# mux_ic.net
KiCad netlist of a schematic drawn in EAGLE
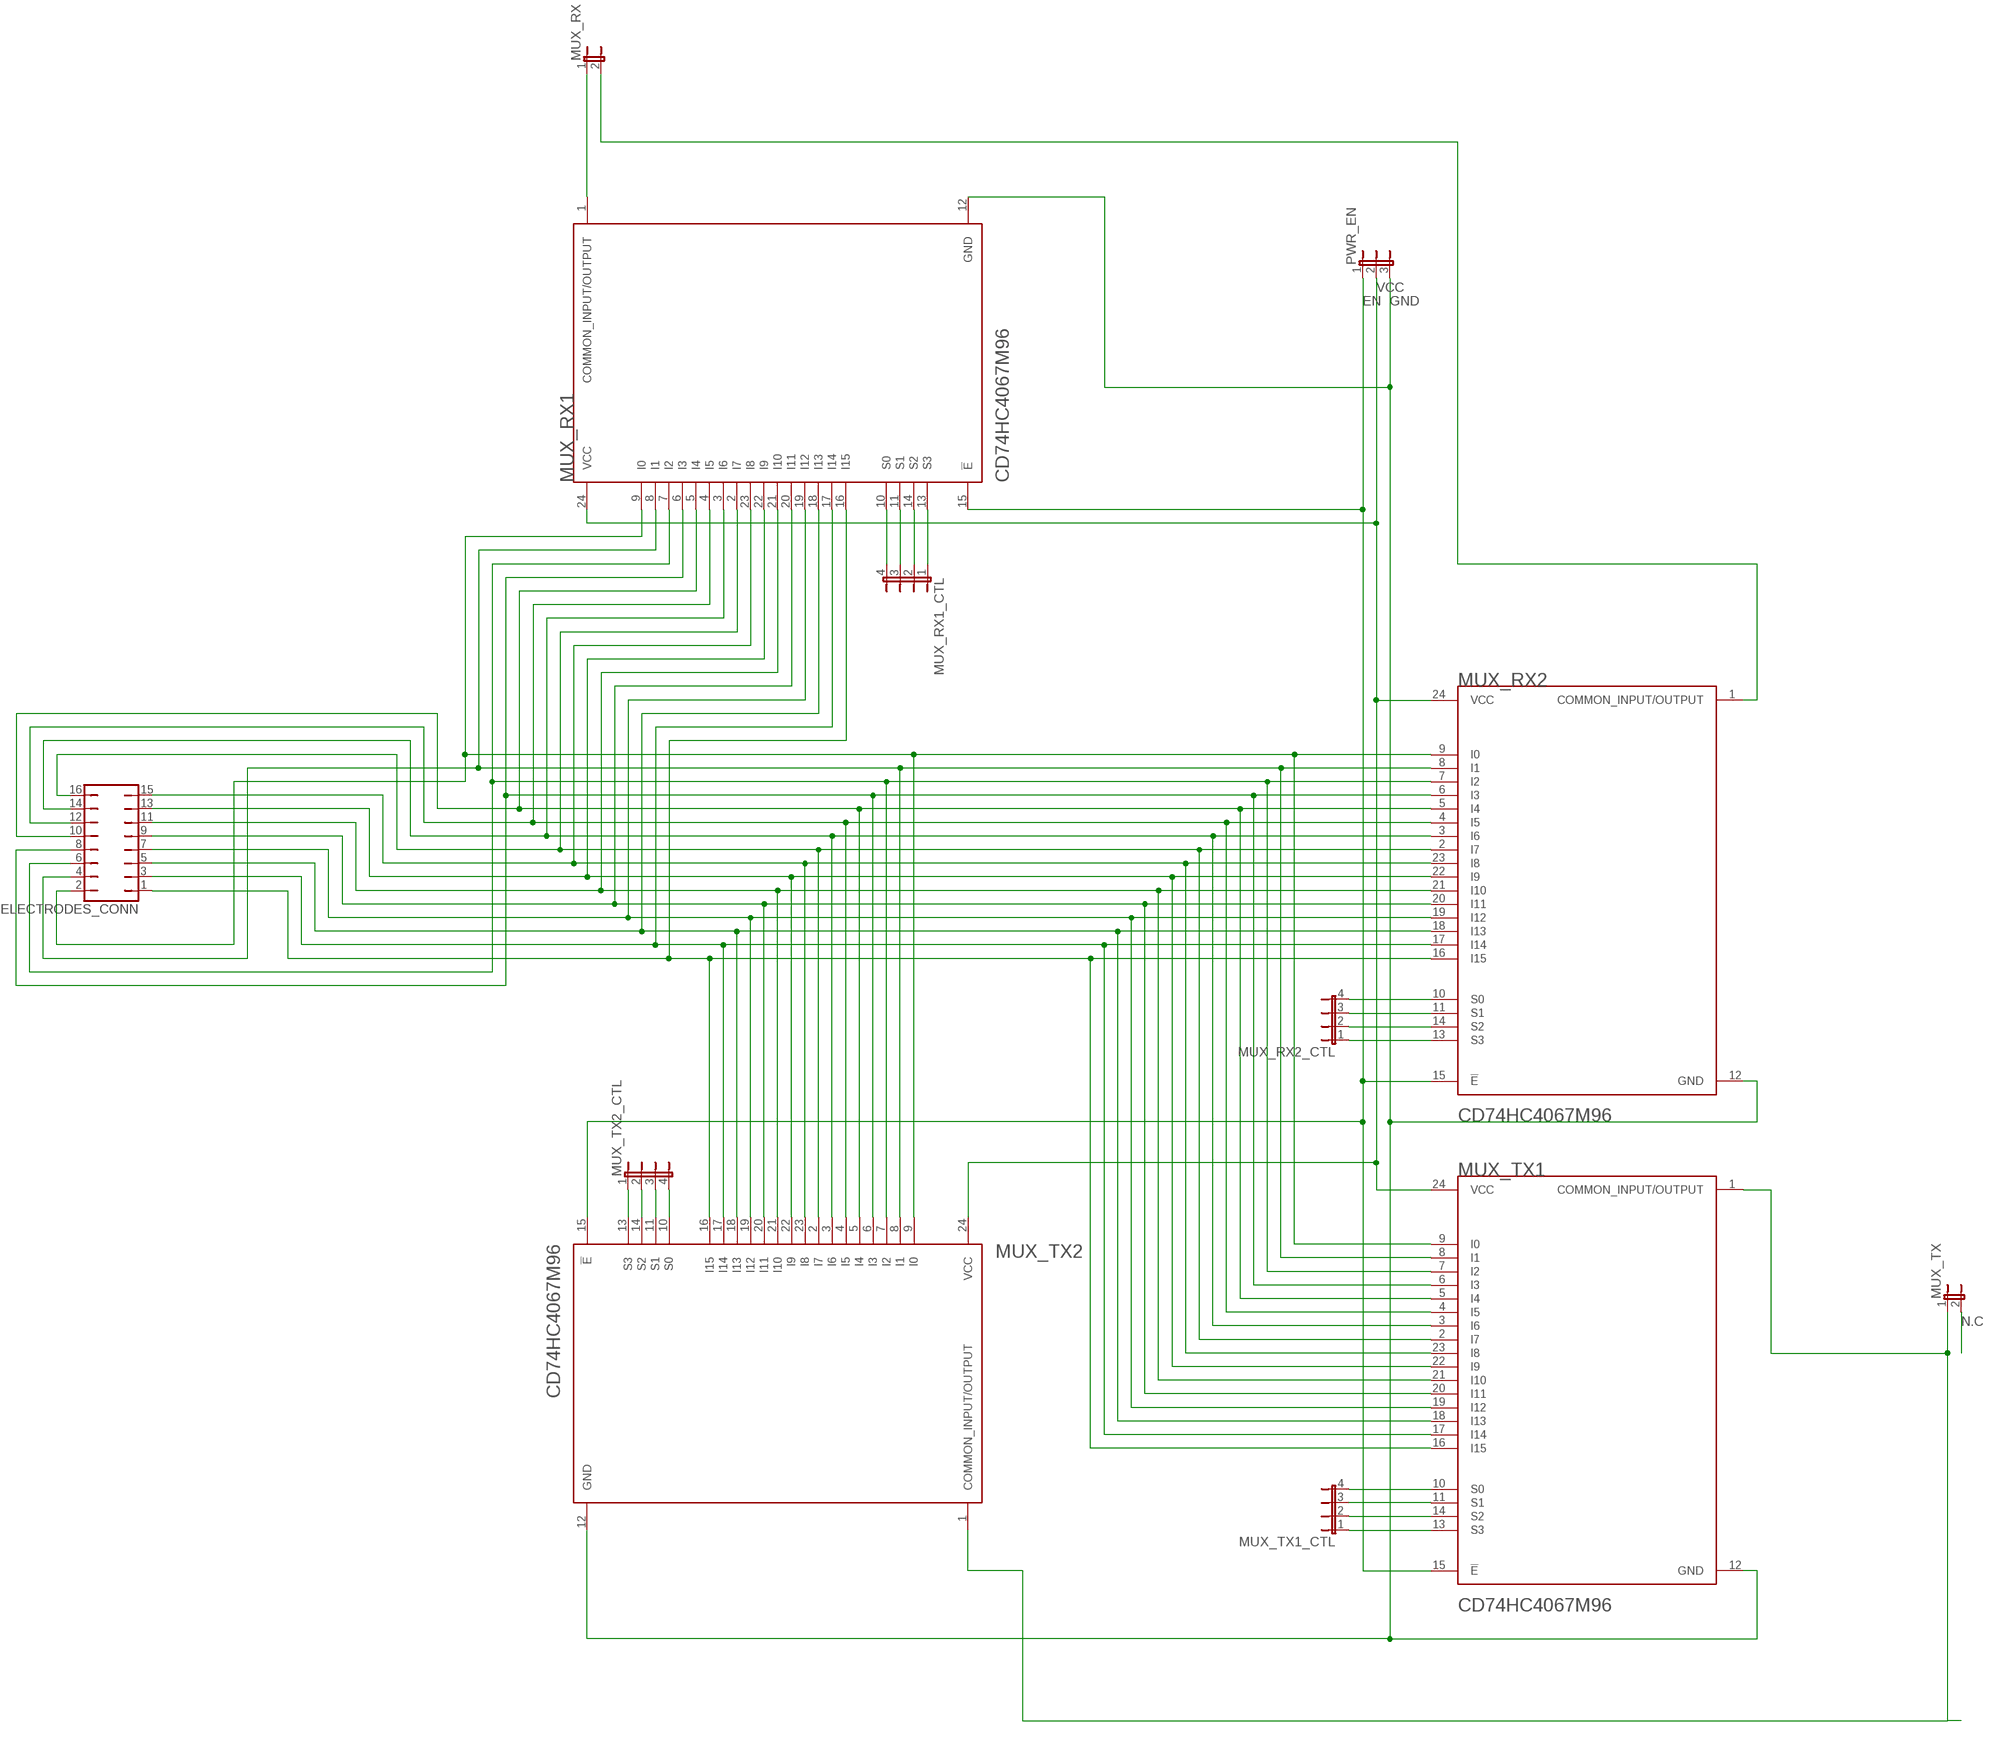
[diagram p0: schematic, sheet 1]

(export (version "E")
  (design (tool "Eeschema 10.0.6"))
  (components
    (comp (ref "ELECTRODES_CONN")
      (value "JP8Q")
      (footprint "eagle-import:JP8Q")
      (libsource (lib "eagle-import") (part "JP8Q"))
    )
    (comp (ref "MUX_RX")
      (value "JP1E")
      (footprint "eagle-import:JP1")
      (libsource (lib "eagle-import") (part "JP1E"))
    )
    (comp (ref "MUX_RX1")
      (value "TEXAS_INSTRUMENTS_CD74HC4067M96TEXAS_INSTRUMENTS_CD74HC4067M96_0_0")
      (footprint "eagle-import:TEXAS_INSTRUMENTS_CD74HC4067M96_0")
      (fields
        (field (name "DIGIKEY_PART_NUMBER") "296-29408-1-ND")
        (field (name "MF") "Texas Instruments")
        (field (name "MOUSER_PART_NUMBER") "595-CD74HC4067M96")
      )
      (libsource (lib "eagle-import") (part "TEXAS_INSTRUMENTS_CD74HC4067M96TEXAS_INSTRUMENTS_CD74HC4067M96_0_0"))
    )
    (comp (ref "MUX_RX1_CTL")
      (value "JP4E")
      (footprint "eagle-import:JP4")
      (libsource (lib "eagle-import") (part "JP4E"))
    )
    (comp (ref "MUX_RX2")
      (value "TEXAS_INSTRUMENTS_CD74HC4067M96TEXAS_INSTRUMENTS_CD74HC4067M96_0_0")
      (footprint "eagle-import:TEXAS_INSTRUMENTS_CD74HC4067M96_0")
      (fields
        (field (name "DIGIKEY_PART_NUMBER") "296-29408-1-ND")
        (field (name "MF") "Texas Instruments")
        (field (name "MOUSER_PART_NUMBER") "595-CD74HC4067M96")
      )
      (libsource (lib "eagle-import") (part "TEXAS_INSTRUMENTS_CD74HC4067M96TEXAS_INSTRUMENTS_CD74HC4067M96_0_0"))
    )
    (comp (ref "MUX_RX2_CTL")
      (value "JP4E")
      (footprint "eagle-import:JP4")
      (libsource (lib "eagle-import") (part "JP4E"))
    )
    (comp (ref "MUX_TX")
      (value "JP1E")
      (footprint "eagle-import:JP1")
      (libsource (lib "eagle-import") (part "JP1E"))
    )
    (comp (ref "MUX_TX1")
      (value "TEXAS_INSTRUMENTS_CD74HC4067M96TEXAS_INSTRUMENTS_CD74HC4067M96_0_0")
      (footprint "eagle-import:TEXAS_INSTRUMENTS_CD74HC4067M96_0")
      (fields
        (field (name "DIGIKEY_PART_NUMBER") "296-29408-1-ND")
        (field (name "MF") "Texas Instruments")
        (field (name "MOUSER_PART_NUMBER") "595-CD74HC4067M96")
      )
      (libsource (lib "eagle-import") (part "TEXAS_INSTRUMENTS_CD74HC4067M96TEXAS_INSTRUMENTS_CD74HC4067M96_0_0"))
    )
    (comp (ref "MUX_TX1_CTL")
      (value "JP4E")
      (footprint "eagle-import:JP4")
      (libsource (lib "eagle-import") (part "JP4E"))
    )
    (comp (ref "MUX_TX2")
      (value "TEXAS_INSTRUMENTS_CD74HC4067M96TEXAS_INSTRUMENTS_CD74HC4067M96_0_0")
      (footprint "eagle-import:TEXAS_INSTRUMENTS_CD74HC4067M96_0")
      (fields
        (field (name "DIGIKEY_PART_NUMBER") "296-29408-1-ND")
        (field (name "MF") "Texas Instruments")
        (field (name "MOUSER_PART_NUMBER") "595-CD74HC4067M96")
      )
      (libsource (lib "eagle-import") (part "TEXAS_INSTRUMENTS_CD74HC4067M96TEXAS_INSTRUMENTS_CD74HC4067M96_0_0"))
    )
    (comp (ref "MUX_TX2_CTL")
      (value "JP4E")
      (footprint "eagle-import:JP4")
      (libsource (lib "eagle-import") (part "JP4E"))
    )
    (comp (ref "PWR_EN")
      (value "JP2W")
      (footprint "eagle-import:JP2W")
      (libsource (lib "eagle-import") (part "JP2W"))
    )
  )
  (nets
    (net (code "1") (name "/EN") (class "Default")
      (node (ref "MUX_RX1") (pin "15") (pinfunction "~{E}_15") (pintype "input"))
      (node (ref "MUX_RX2") (pin "15") (pinfunction "~{E}_15") (pintype "input"))
      (node (ref "MUX_TX1") (pin "15") (pinfunction "~{E}_15") (pintype "input"))
      (node (ref "MUX_TX2") (pin "15") (pinfunction "~{E}_15") (pintype "input"))
      (node (ref "PWR_EN") (pin "1") (pinfunction "1_1") (pintype "passive"))
    )
    (net (code "2") (name "/GND") (class "Default")
      (node (ref "MUX_RX1") (pin "12") (pinfunction "GND_12") (pintype "power_in"))
      (node (ref "MUX_RX2") (pin "12") (pinfunction "GND_12") (pintype "power_in"))
      (node (ref "MUX_TX1") (pin "12") (pinfunction "GND_12") (pintype "power_in"))
      (node (ref "MUX_TX2") (pin "12") (pinfunction "GND_12") (pintype "power_in"))
      (node (ref "PWR_EN") (pin "3") (pinfunction "3_3") (pintype "passive"))
    )
    (net (code "3") (name "/N$2") (class "Default")
      (node (ref "ELECTRODES_CONN") (pin "1") (pinfunction "1_1") (pintype "passive"))
      (node (ref "ELECTRODES_CONN") (pin "10") (pinfunction "10_10") (pintype "passive"))
      (node (ref "ELECTRODES_CONN") (pin "12") (pinfunction "12_12") (pintype "passive"))
      (node (ref "ELECTRODES_CONN") (pin "13") (pinfunction "13_13") (pintype "passive"))
      (node (ref "ELECTRODES_CONN") (pin "14") (pinfunction "14_14") (pintype "passive"))
      (node (ref "ELECTRODES_CONN") (pin "15") (pinfunction "15_15") (pintype "passive"))
      (node (ref "ELECTRODES_CONN") (pin "16") (pinfunction "16_16") (pintype "passive"))
      (node (ref "ELECTRODES_CONN") (pin "3") (pinfunction "3_3") (pintype "passive"))
      (node (ref "ELECTRODES_CONN") (pin "4") (pinfunction "4_4") (pintype "passive"))
      (node (ref "ELECTRODES_CONN") (pin "5") (pinfunction "5_5") (pintype "passive"))
      (node (ref "ELECTRODES_CONN") (pin "6") (pinfunction "6_6") (pintype "passive"))
      (node (ref "ELECTRODES_CONN") (pin "7") (pinfunction "7_7") (pintype "passive"))
      (node (ref "ELECTRODES_CONN") (pin "8") (pinfunction "8_8") (pintype "passive"))
      (node (ref "ELECTRODES_CONN") (pin "9") (pinfunction "9_9") (pintype "passive"))
      (node (ref "MUX_RX1") (pin "16") (pinfunction "I15_16") (pintype "input"))
      (node (ref "MUX_RX1") (pin "17") (pinfunction "I14_17") (pintype "input"))
      (node (ref "MUX_RX1") (pin "18") (pinfunction "I13_18") (pintype "input"))
      (node (ref "MUX_RX1") (pin "19") (pinfunction "I12_19") (pintype "input"))
      (node (ref "MUX_RX1") (pin "2") (pinfunction "I7_2") (pintype "input"))
      (node (ref "MUX_RX1") (pin "20") (pinfunction "I11_20") (pintype "input"))
      (node (ref "MUX_RX1") (pin "22") (pinfunction "I9_22") (pintype "input"))
      (node (ref "MUX_RX1") (pin "23") (pinfunction "I8_23") (pintype "input"))
      (node (ref "MUX_RX1") (pin "3") (pinfunction "I6_3") (pintype "input"))
      (node (ref "MUX_RX1") (pin "4") (pinfunction "I5_4") (pintype "input"))
      (node (ref "MUX_RX1") (pin "5") (pinfunction "I4_5") (pintype "input"))
      (node (ref "MUX_RX1") (pin "6") (pinfunction "I3_6") (pintype "input"))
      (node (ref "MUX_RX1") (pin "7") (pinfunction "I2_7") (pintype "input"))
      (node (ref "MUX_RX1") (pin "8") (pinfunction "I1_8") (pintype "input"))
      (node (ref "MUX_RX2") (pin "16") (pinfunction "I15_16") (pintype "input"))
      (node (ref "MUX_RX2") (pin "17") (pinfunction "I14_17") (pintype "input"))
      (node (ref "MUX_RX2") (pin "18") (pinfunction "I13_18") (pintype "input"))
      (node (ref "MUX_RX2") (pin "19") (pinfunction "I12_19") (pintype "input"))
      (node (ref "MUX_RX2") (pin "2") (pinfunction "I7_2") (pintype "input"))
      (node (ref "MUX_RX2") (pin "20") (pinfunction "I11_20") (pintype "input"))
      (node (ref "MUX_RX2") (pin "22") (pinfunction "I9_22") (pintype "input"))
      (node (ref "MUX_RX2") (pin "23") (pinfunction "I8_23") (pintype "input"))
      (node (ref "MUX_RX2") (pin "3") (pinfunction "I6_3") (pintype "input"))
      (node (ref "MUX_RX2") (pin "4") (pinfunction "I5_4") (pintype "input"))
      (node (ref "MUX_RX2") (pin "5") (pinfunction "I4_5") (pintype "input"))
      (node (ref "MUX_RX2") (pin "6") (pinfunction "I3_6") (pintype "input"))
      (node (ref "MUX_RX2") (pin "7") (pinfunction "I2_7") (pintype "input"))
      (node (ref "MUX_RX2") (pin "8") (pinfunction "I1_8") (pintype "input"))
      (node (ref "MUX_TX1") (pin "16") (pinfunction "I15_16") (pintype "input"))
      (node (ref "MUX_TX1") (pin "17") (pinfunction "I14_17") (pintype "input"))
      (node (ref "MUX_TX1") (pin "18") (pinfunction "I13_18") (pintype "input"))
      (node (ref "MUX_TX1") (pin "19") (pinfunction "I12_19") (pintype "input"))
      (node (ref "MUX_TX1") (pin "2") (pinfunction "I7_2") (pintype "input"))
      (node (ref "MUX_TX1") (pin "20") (pinfunction "I11_20") (pintype "input"))
      (node (ref "MUX_TX1") (pin "22") (pinfunction "I9_22") (pintype "input"))
      (node (ref "MUX_TX1") (pin "23") (pinfunction "I8_23") (pintype "input"))
      (node (ref "MUX_TX1") (pin "3") (pinfunction "I6_3") (pintype "input"))
      (node (ref "MUX_TX1") (pin "4") (pinfunction "I5_4") (pintype "input"))
      (node (ref "MUX_TX1") (pin "5") (pinfunction "I4_5") (pintype "input"))
      (node (ref "MUX_TX1") (pin "6") (pinfunction "I3_6") (pintype "input"))
      (node (ref "MUX_TX1") (pin "7") (pinfunction "I2_7") (pintype "input"))
      (node (ref "MUX_TX1") (pin "8") (pinfunction "I1_8") (pintype "input"))
      (node (ref "MUX_TX2") (pin "16") (pinfunction "I15_16") (pintype "input"))
      (node (ref "MUX_TX2") (pin "17") (pinfunction "I14_17") (pintype "input"))
      (node (ref "MUX_TX2") (pin "18") (pinfunction "I13_18") (pintype "input"))
      (node (ref "MUX_TX2") (pin "19") (pinfunction "I12_19") (pintype "input"))
      (node (ref "MUX_TX2") (pin "2") (pinfunction "I7_2") (pintype "input"))
      (node (ref "MUX_TX2") (pin "20") (pinfunction "I11_20") (pintype "input"))
      (node (ref "MUX_TX2") (pin "22") (pinfunction "I9_22") (pintype "input"))
      (node (ref "MUX_TX2") (pin "23") (pinfunction "I8_23") (pintype "input"))
      (node (ref "MUX_TX2") (pin "3") (pinfunction "I6_3") (pintype "input"))
      (node (ref "MUX_TX2") (pin "4") (pinfunction "I5_4") (pintype "input"))
      (node (ref "MUX_TX2") (pin "5") (pinfunction "I4_5") (pintype "input"))
      (node (ref "MUX_TX2") (pin "6") (pinfunction "I3_6") (pintype "input"))
      (node (ref "MUX_TX2") (pin "7") (pinfunction "I2_7") (pintype "input"))
      (node (ref "MUX_TX2") (pin "8") (pinfunction "I1_8") (pintype "input"))
    )
    (net (code "4") (name "/N.C") (class "Default")
      (node (ref "MUX_TX") (pin "2") (pinfunction "2_2") (pintype "passive"))
    )
    (net (code "5") (name "/VCC") (class "Default")
      (node (ref "MUX_RX1") (pin "24") (pinfunction "VCC_24") (pintype "power_in"))
      (node (ref "MUX_RX2") (pin "24") (pinfunction "VCC_24") (pintype "power_in"))
      (node (ref "MUX_TX1") (pin "24") (pinfunction "VCC_24") (pintype "power_in"))
      (node (ref "MUX_TX2") (pin "24") (pinfunction "VCC_24") (pintype "power_in"))
      (node (ref "PWR_EN") (pin "2") (pinfunction "2_2") (pintype "passive"))
    )
    (net (code "6") (name "Net-(MUX_RX1-COMMON_INPUT{slash}OUTPUT)") (class "Default")
      (node (ref "MUX_RX") (pin "1") (pinfunction "1_1") (pintype "passive"))
      (node (ref "MUX_RX1") (pin "1") (pinfunction "COMMON_INPUT/OUTPUT_1") (pintype "bidirectional"))
    )
    (net (code "7") (name "Net-(MUX_RX1-I0)") (class "Default")
      (node (ref "ELECTRODES_CONN") (pin "2") (pinfunction "2_2") (pintype "passive"))
      (node (ref "MUX_RX1") (pin "9") (pinfunction "I0_9") (pintype "input"))
      (node (ref "MUX_RX2") (pin "9") (pinfunction "I0_9") (pintype "input"))
      (node (ref "MUX_TX1") (pin "9") (pinfunction "I0_9") (pintype "input"))
      (node (ref "MUX_TX2") (pin "9") (pinfunction "I0_9") (pintype "input"))
    )
    (net (code "8") (name "Net-(MUX_RX1-I10)") (class "Default")
      (node (ref "ELECTRODES_CONN") (pin "11") (pinfunction "11_11") (pintype "passive"))
      (node (ref "MUX_RX1") (pin "21") (pinfunction "I10_21") (pintype "input"))
      (node (ref "MUX_RX2") (pin "21") (pinfunction "I10_21") (pintype "input"))
      (node (ref "MUX_TX1") (pin "21") (pinfunction "I10_21") (pintype "input"))
      (node (ref "MUX_TX2") (pin "21") (pinfunction "I10_21") (pintype "input"))
    )
    (net (code "9") (name "Net-(MUX_RX1-S0)") (class "Default")
      (node (ref "MUX_RX1") (pin "10") (pinfunction "S0_10") (pintype "input"))
      (node (ref "MUX_RX1_CTL") (pin "4") (pinfunction "4_4") (pintype "passive"))
    )
    (net (code "10") (name "Net-(MUX_RX1-S1)") (class "Default")
      (node (ref "MUX_RX1") (pin "11") (pinfunction "S1_11") (pintype "input"))
      (node (ref "MUX_RX1_CTL") (pin "3") (pinfunction "3_3") (pintype "passive"))
    )
    (net (code "11") (name "Net-(MUX_RX1-S2)") (class "Default")
      (node (ref "MUX_RX1") (pin "14") (pinfunction "S2_14") (pintype "input"))
      (node (ref "MUX_RX1_CTL") (pin "2") (pinfunction "2_2") (pintype "passive"))
    )
    (net (code "12") (name "Net-(MUX_RX1-S3)") (class "Default")
      (node (ref "MUX_RX1") (pin "13") (pinfunction "S3_13") (pintype "input"))
      (node (ref "MUX_RX1_CTL") (pin "1") (pinfunction "1_1") (pintype "passive"))
    )
    (net (code "13") (name "Net-(MUX_RX2-COMMON_INPUT{slash}OUTPUT)") (class "Default")
      (node (ref "MUX_RX") (pin "2") (pinfunction "2_2") (pintype "passive"))
      (node (ref "MUX_RX2") (pin "1") (pinfunction "COMMON_INPUT/OUTPUT_1") (pintype "bidirectional"))
    )
    (net (code "14") (name "Net-(MUX_RX2-S0)") (class "Default")
      (node (ref "MUX_RX2") (pin "10") (pinfunction "S0_10") (pintype "input"))
      (node (ref "MUX_RX2_CTL") (pin "4") (pinfunction "4_4") (pintype "passive"))
    )
    (net (code "15") (name "Net-(MUX_RX2-S1)") (class "Default")
      (node (ref "MUX_RX2") (pin "11") (pinfunction "S1_11") (pintype "input"))
      (node (ref "MUX_RX2_CTL") (pin "3") (pinfunction "3_3") (pintype "passive"))
    )
    (net (code "16") (name "Net-(MUX_RX2-S2)") (class "Default")
      (node (ref "MUX_RX2") (pin "14") (pinfunction "S2_14") (pintype "input"))
      (node (ref "MUX_RX2_CTL") (pin "2") (pinfunction "2_2") (pintype "passive"))
    )
    (net (code "17") (name "Net-(MUX_RX2-S3)") (class "Default")
      (node (ref "MUX_RX2") (pin "13") (pinfunction "S3_13") (pintype "input"))
      (node (ref "MUX_RX2_CTL") (pin "1") (pinfunction "1_1") (pintype "passive"))
    )
    (net (code "18") (name "Net-(MUX_TX1-COMMON_INPUT{slash}OUTPUT)") (class "Default")
      (node (ref "MUX_TX") (pin "1") (pinfunction "1_1") (pintype "passive"))
      (node (ref "MUX_TX1") (pin "1") (pinfunction "COMMON_INPUT/OUTPUT_1") (pintype "bidirectional"))
      (node (ref "MUX_TX2") (pin "1") (pinfunction "COMMON_INPUT/OUTPUT_1") (pintype "bidirectional"))
    )
    (net (code "19") (name "Net-(MUX_TX1-S0)") (class "Default")
      (node (ref "MUX_TX1") (pin "10") (pinfunction "S0_10") (pintype "input"))
      (node (ref "MUX_TX1_CTL") (pin "4") (pinfunction "4_4") (pintype "passive"))
    )
    (net (code "20") (name "Net-(MUX_TX1-S1)") (class "Default")
      (node (ref "MUX_TX1") (pin "11") (pinfunction "S1_11") (pintype "input"))
      (node (ref "MUX_TX1_CTL") (pin "3") (pinfunction "3_3") (pintype "passive"))
    )
    (net (code "21") (name "Net-(MUX_TX1-S2)") (class "Default")
      (node (ref "MUX_TX1") (pin "14") (pinfunction "S2_14") (pintype "input"))
      (node (ref "MUX_TX1_CTL") (pin "2") (pinfunction "2_2") (pintype "passive"))
    )
    (net (code "22") (name "Net-(MUX_TX1-S3)") (class "Default")
      (node (ref "MUX_TX1") (pin "13") (pinfunction "S3_13") (pintype "input"))
      (node (ref "MUX_TX1_CTL") (pin "1") (pinfunction "1_1") (pintype "passive"))
    )
    (net (code "23") (name "Net-(MUX_TX2-S0)") (class "Default")
      (node (ref "MUX_TX2") (pin "10") (pinfunction "S0_10") (pintype "input"))
      (node (ref "MUX_TX2_CTL") (pin "4") (pinfunction "4_4") (pintype "passive"))
    )
    (net (code "24") (name "Net-(MUX_TX2-S1)") (class "Default")
      (node (ref "MUX_TX2") (pin "11") (pinfunction "S1_11") (pintype "input"))
      (node (ref "MUX_TX2_CTL") (pin "3") (pinfunction "3_3") (pintype "passive"))
    )
    (net (code "25") (name "Net-(MUX_TX2-S2)") (class "Default")
      (node (ref "MUX_TX2") (pin "14") (pinfunction "S2_14") (pintype "input"))
      (node (ref "MUX_TX2_CTL") (pin "2") (pinfunction "2_2") (pintype "passive"))
    )
    (net (code "26") (name "Net-(MUX_TX2-S3)") (class "Default")
      (node (ref "MUX_TX2") (pin "13") (pinfunction "S3_13") (pintype "input"))
      (node (ref "MUX_TX2_CTL") (pin "1") (pinfunction "1_1") (pintype "passive"))
    )
  )
)
